# ScreenCircuitV1.net
KiCad netlist of a schematic drawn in EAGLE
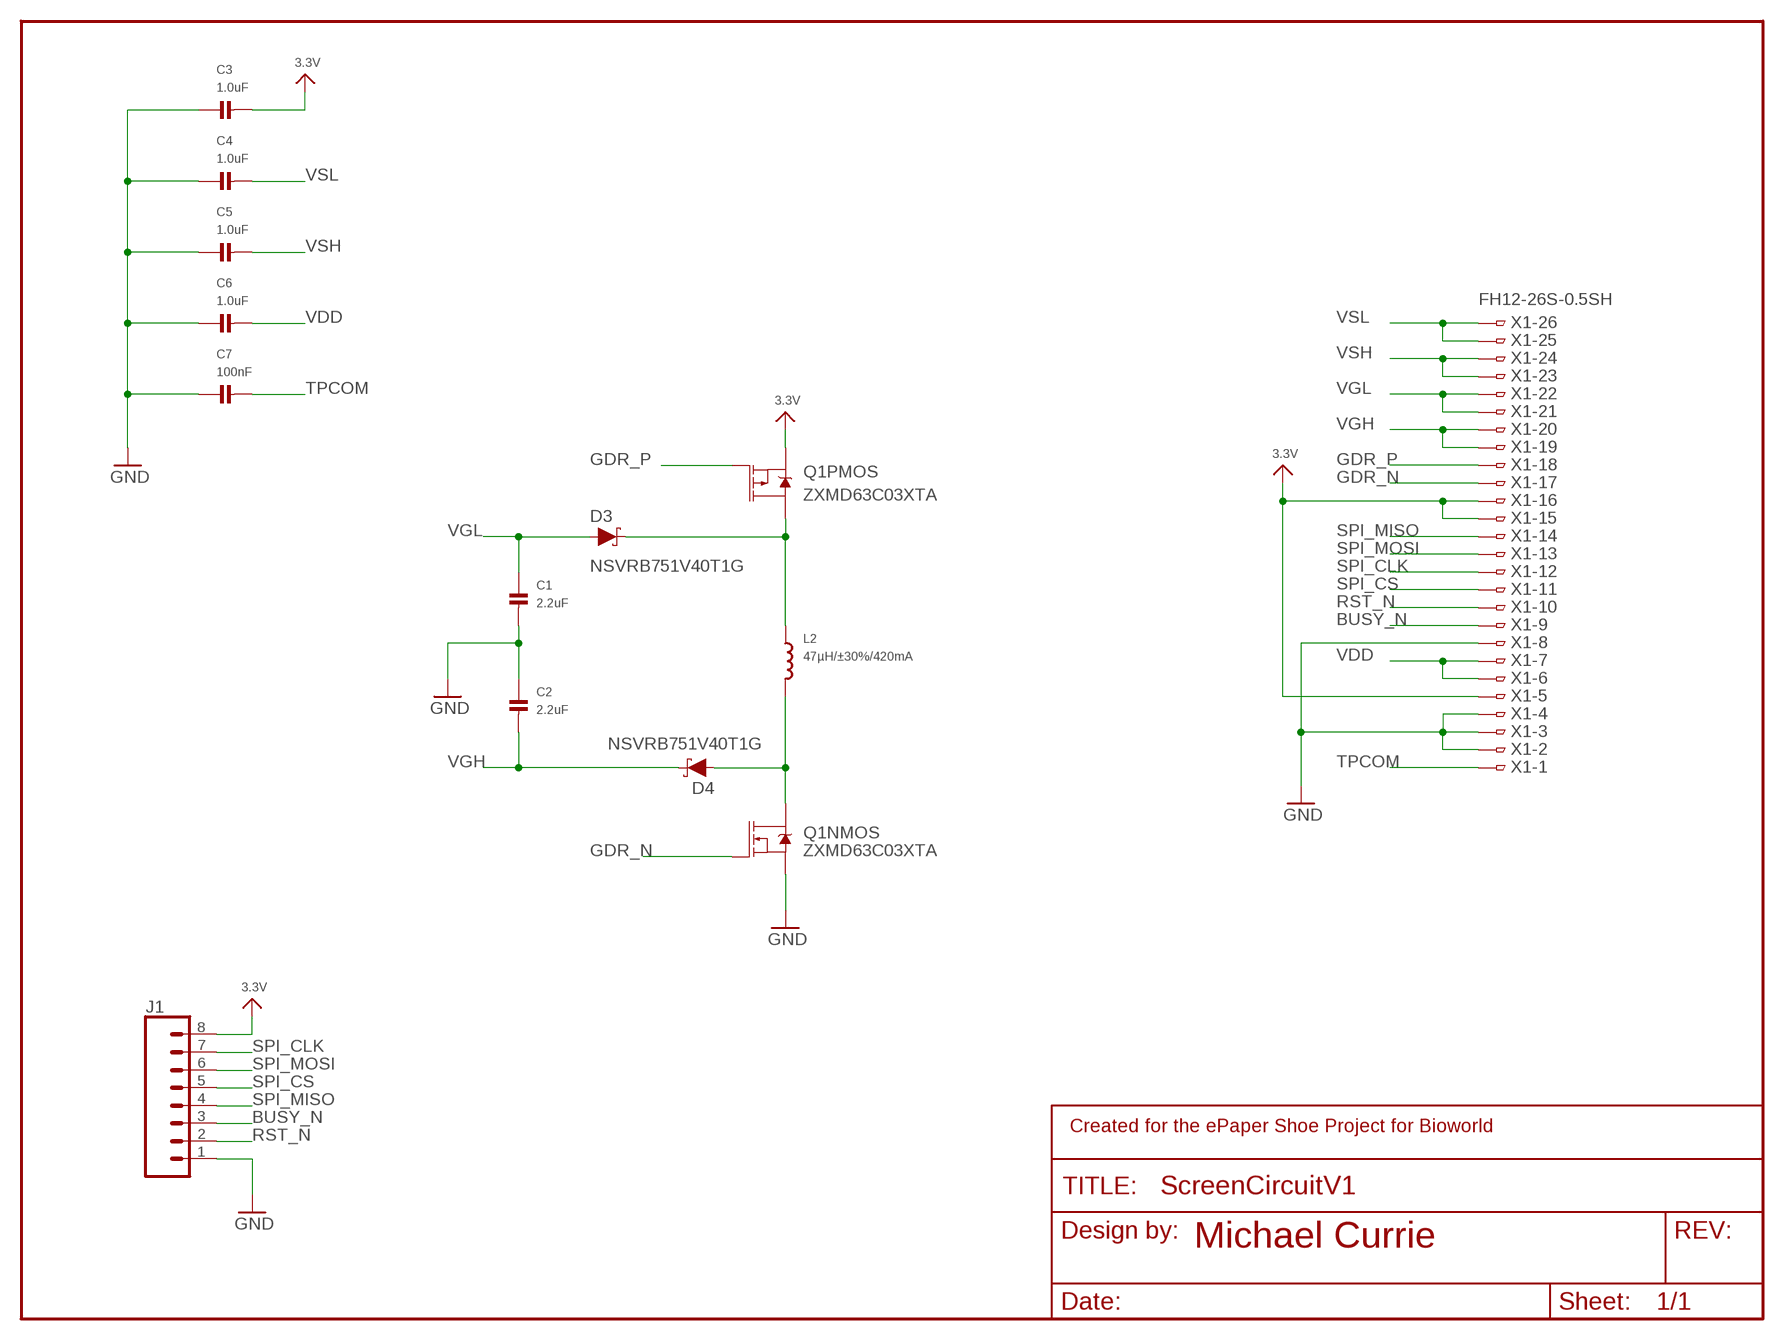
[diagram p0: schematic, sheet 1]

(export (version "E")
  (design (tool "Eeschema 10.0.6"))
  (components
    (comp (ref "C1")
      (value "2.2uF")
      (footprint "eagle-import:0805")
      (libsource (lib "eagle-import") (part "CAP_CERAMIC0805"))
    )
    (comp (ref "C2")
      (value "2.2uF")
      (footprint "eagle-import:0805")
      (libsource (lib "eagle-import") (part "CAP_CERAMIC0805"))
    )
    (comp (ref "C3")
      (value "1.0uF")
      (footprint "eagle-import:0805")
      (libsource (lib "eagle-import") (part "CAP_CERAMIC0805"))
    )
    (comp (ref "C4")
      (value "1.0uF")
      (footprint "eagle-import:0805")
      (libsource (lib "eagle-import") (part "CAP_CERAMIC0805"))
    )
    (comp (ref "C5")
      (value "1.0uF")
      (footprint "eagle-import:0805")
      (libsource (lib "eagle-import") (part "CAP_CERAMIC0805"))
    )
    (comp (ref "C6")
      (value "1.0uF")
      (footprint "eagle-import:0805")
      (libsource (lib "eagle-import") (part "CAP_CERAMIC0805"))
    )
    (comp (ref "C7")
      (value "100nF")
      (footprint "eagle-import:0805")
      (libsource (lib "eagle-import") (part "CAP_CERAMIC0805"))
    )
    (comp (ref "D3")
      (value "0.5A/40V/420mV")
      (footprint "eagle-import:SOD-323")
      (libsource (lib "eagle-import") (part "DIODE-SCHOTTKY-PMEG4005EJ"))
    )
    (comp (ref "D4")
      (value "0.5A/40V/420mV")
      (footprint "eagle-import:SOD-323")
      (libsource (lib "eagle-import") (part "DIODE-SCHOTTKY-PMEG4005EJ"))
    )
    (comp (ref "FRAME1")
      (value "FRAME-LETTER-MICHAELNO_PACKAGE")
      (footprint "eagle-import:DUMMY")
      (fields (field (name "DESIGNER") "Nobody"))
      (libsource (lib "eagle-import") (part "FRAME-LETTER-MICHAELNO_PACKAGE"))
    )
    (comp (ref "J1")
      (value "CONN_08\"")
      (footprint "eagle-import:1X08")
      (libsource (lib "eagle-import") (part "CONN_08{dblquote}"))
    )
    (comp (ref "L2")
      (value "47µH/±30%/420mA")
      (footprint "eagle-import:INDUCTOR_5X5MM_NR5040_NOTHERMALS")
      (libsource (lib "eagle-import") (part "INDUCTORNR5040"))
    )
    (comp (ref "Q1")
      (value "IRF7509")
      (footprint "eagle-import:MSOP8")
      (libsource (lib "eagle-import") (part "IRF7509"))
    )
    (comp (ref "X1")
      (value "FH12-26S-0.5SH")
      (footprint "eagle-import:FH12-26S-0.5SH")
      (fields (field (name "MPN") "FH12-26S-0.5SH(55)"))
      (libsource (lib "eagle-import") (part "FH12-26S-0.5SH"))
    )
  )
  (nets
    (net (code "1") (name "/BUSY_N") (class "Default")
      (node (ref "J1") (pin "3") (pinfunction "3_3") (pintype "passive"))
      (node (ref "X1") (pin "9") (pinfunction "1_9") (pintype "passive"))
    )
    (net (code "2") (name "/GDR_N") (class "Default")
      (node (ref "Q1") (pin "2") (pinfunction "G_2") (pintype "bidirectional"))
      (node (ref "X1") (pin "17") (pinfunction "1_17") (pintype "passive"))
    )
    (net (code "3") (name "/GDR_P") (class "Default")
      (node (ref "Q1") (pin "4") (pinfunction "G_4") (pintype "bidirectional"))
      (node (ref "X1") (pin "18") (pinfunction "1_18") (pintype "passive"))
    )
    (net (code "4") (name "/RST_N") (class "Default")
      (node (ref "J1") (pin "2") (pinfunction "2_2") (pintype "passive"))
      (node (ref "X1") (pin "10") (pinfunction "1_10") (pintype "passive"))
    )
    (net (code "5") (name "/SPI_CLK") (class "Default")
      (node (ref "J1") (pin "7") (pinfunction "7_7") (pintype "passive"))
      (node (ref "X1") (pin "12") (pinfunction "1_12") (pintype "passive"))
    )
    (net (code "6") (name "/SPI_CS") (class "Default")
      (node (ref "J1") (pin "5") (pinfunction "5_5") (pintype "passive"))
      (node (ref "X1") (pin "11") (pinfunction "1_11") (pintype "passive"))
    )
    (net (code "7") (name "/SPI_MISO") (class "Default")
      (node (ref "J1") (pin "4") (pinfunction "4_4") (pintype "passive"))
      (node (ref "X1") (pin "14") (pinfunction "1_14") (pintype "passive"))
    )
    (net (code "8") (name "/SPI_MOSI") (class "Default")
      (node (ref "J1") (pin "6") (pinfunction "6_6") (pintype "passive"))
      (node (ref "X1") (pin "13") (pinfunction "1_13") (pintype "passive"))
    )
    (net (code "9") (name "/TPCOM") (class "Default")
      (node (ref "C7") (pin "2") (pinfunction "P$2_2") (pintype "passive"))
      (node (ref "X1") (pin "1") (pinfunction "1_1") (pintype "passive"))
    )
    (net (code "10") (name "/VDD") (class "Default")
      (node (ref "C6") (pin "2") (pinfunction "P$2_2") (pintype "passive"))
      (node (ref "X1") (pin "6") (pinfunction "1_6") (pintype "passive"))
      (node (ref "X1") (pin "7") (pinfunction "1_7") (pintype "passive"))
    )
    (net (code "11") (name "/VGH") (class "Default")
      (node (ref "C2") (pin "2") (pinfunction "P$2_2") (pintype "passive"))
      (node (ref "D4") (pin "C") (pinfunction "C_C") (pintype "passive"))
      (node (ref "X1") (pin "19") (pinfunction "1_19") (pintype "passive"))
      (node (ref "X1") (pin "20") (pinfunction "1_20") (pintype "passive"))
    )
    (net (code "12") (name "/VGL") (class "Default")
      (node (ref "C1") (pin "1") (pinfunction "P$1_1") (pintype "passive"))
      (node (ref "D3") (pin "A") (pinfunction "A_A") (pintype "passive"))
      (node (ref "X1") (pin "21") (pinfunction "1_21") (pintype "passive"))
      (node (ref "X1") (pin "22") (pinfunction "1_22") (pintype "passive"))
    )
    (net (code "13") (name "/VSH") (class "Default")
      (node (ref "C5") (pin "2") (pinfunction "P$2_2") (pintype "passive"))
      (node (ref "X1") (pin "23") (pinfunction "1_23") (pintype "passive"))
      (node (ref "X1") (pin "24") (pinfunction "1_24") (pintype "passive"))
    )
    (net (code "14") (name "/VSL") (class "Default")
      (node (ref "C4") (pin "2") (pinfunction "P$2_2") (pintype "passive"))
      (node (ref "X1") (pin "25") (pinfunction "1_25") (pintype "passive"))
      (node (ref "X1") (pin "26") (pinfunction "1_26") (pintype "passive"))
    )
    (net (code "15") (name "3.3V") (class "Default")
      (node (ref "C3") (pin "2") (pinfunction "P$2_2") (pintype "passive"))
      (node (ref "J1") (pin "8") (pinfunction "8_8") (pintype "passive"))
      (node (ref "Q1") (pin "3") (pinfunction "S_3") (pintype "bidirectional"))
      (node (ref "X1") (pin "15") (pinfunction "1_15") (pintype "passive"))
      (node (ref "X1") (pin "16") (pinfunction "1_16") (pintype "passive"))
      (node (ref "X1") (pin "5") (pinfunction "1_5") (pintype "passive"))
    )
    (net (code "16") (name "GND") (class "Default")
      (node (ref "C1") (pin "2") (pinfunction "P$2_2") (pintype "passive"))
      (node (ref "C2") (pin "1") (pinfunction "P$1_1") (pintype "passive"))
      (node (ref "C3") (pin "1") (pinfunction "P$1_1") (pintype "passive"))
      (node (ref "C4") (pin "1") (pinfunction "P$1_1") (pintype "passive"))
      (node (ref "C5") (pin "1") (pinfunction "P$1_1") (pintype "passive"))
      (node (ref "C6") (pin "1") (pinfunction "P$1_1") (pintype "passive"))
      (node (ref "C7") (pin "1") (pinfunction "P$1_1") (pintype "passive"))
      (node (ref "J1") (pin "1") (pinfunction "1_1") (pintype "passive"))
      (node (ref "Q1") (pin "1") (pinfunction "S_1") (pintype "bidirectional"))
      (node (ref "X1") (pin "2") (pinfunction "1_2") (pintype "passive"))
      (node (ref "X1") (pin "3") (pinfunction "1_3") (pintype "passive"))
      (node (ref "X1") (pin "4") (pinfunction "1_4") (pintype "passive"))
      (node (ref "X1") (pin "8") (pinfunction "1_8") (pintype "passive"))
    )
    (net (code "17") (name "Net-(L2-1)") (class "Default")
      (node (ref "D3") (pin "C") (pinfunction "C_C") (pintype "passive"))
      (node (ref "L2") (pin "P$1") (pinfunction "1_P$1") (pintype "passive"))
      (node (ref "Q1") (pin "5") (pinfunction "D_5") (pintype "bidirectional"))
      (node (ref "Q1") (pin "6") (pinfunction "D_6") (pintype "bidirectional"))
    )
    (net (code "18") (name "Net-(L2-2)") (class "Default")
      (node (ref "D4") (pin "A") (pinfunction "A_A") (pintype "passive"))
      (node (ref "L2") (pin "P$2") (pinfunction "2_P$2") (pintype "passive"))
      (node (ref "Q1") (pin "7") (pinfunction "D_7") (pintype "bidirectional"))
      (node (ref "Q1") (pin "8") (pinfunction "D_8") (pintype "bidirectional"))
    )
  )
)
